# 5vacd.net
KiCad netlist of a schematic drawn in EAGLE
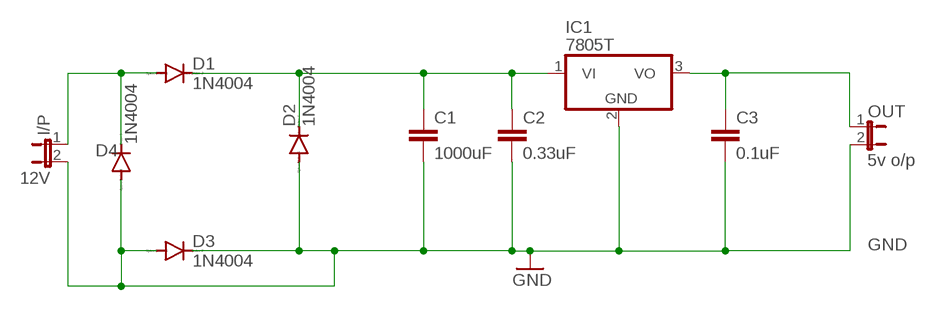
[diagram p0: schematic, sheet 1]

(export (version "E")
  (design (tool "Eeschema 10.0.6"))
  (components
    (comp (ref "C1")
      (value "1000uF")
      (footprint "eagle-import:C2.5-3")
      (fields (field (name "POPULARITY") "1000"))
      (libsource (lib "eagle-import") (part "C2,5-3"))
    )
    (comp (ref "C2")
      (value "0.33uF")
      (footprint "eagle-import:C2.5-3")
      (libsource (lib "eagle-import") (part "C2,5-3"))
    )
    (comp (ref "C3")
      (value "0.1uF")
      (footprint "eagle-import:C2.5-3")
      (libsource (lib "eagle-import") (part "C2,5-3"))
    )
    (comp (ref "D1")
      (value "1N4004")
      (footprint "eagle-import:DO41-10")
      (libsource (lib "eagle-import") (part "1N4004"))
    )
    (comp (ref "D2")
      (value "1N4004")
      (footprint "eagle-import:DO41-10")
      (libsource (lib "eagle-import") (part "1N4004"))
    )
    (comp (ref "D3")
      (value "1N4004")
      (footprint "eagle-import:DO41-10")
      (libsource (lib "eagle-import") (part "1N4004"))
    )
    (comp (ref "D4")
      (value "1N4004")
      (footprint "eagle-import:DO41-10")
      (libsource (lib "eagle-import") (part "1N4004"))
    )
    (comp (ref "I/P")
      (value "12V")
      (footprint "eagle-import:JP1")
      (libsource (lib "eagle-import") (part "JP1E"))
    )
    (comp (ref "IC1")
      (value "7805T")
      (footprint "eagle-import:TO220H")
      (libsource (lib "eagle-import") (part "78T05"))
    )
    (comp (ref "OUT")
      (value "5v o/p")
      (footprint "eagle-import:JP1")
      (libsource (lib "eagle-import") (part "JP1E"))
    )
  )
  (nets
    (net (code "1") (name "GND") (class "Default")
      (node (ref "C1") (pin "2") (pinfunction "2_2") (pintype "passive"))
      (node (ref "C2") (pin "2") (pinfunction "2_2") (pintype "passive"))
      (node (ref "C3") (pin "2") (pinfunction "2_2") (pintype "passive"))
      (node (ref "D2") (pin "A") (pinfunction "A_A") (pintype "passive"))
      (node (ref "D3") (pin "A") (pinfunction "A_A") (pintype "passive"))
      (node (ref "D3") (pin "C") (pinfunction "C_C") (pintype "passive"))
      (node (ref "D4") (pin "A") (pinfunction "A_A") (pintype "passive"))
      (node (ref "I/P") (pin "2") (pinfunction "2_2") (pintype "passive"))
      (node (ref "IC1") (pin "2") (pinfunction "GND_2") (pintype "passive"))
      (node (ref "OUT") (pin "2") (pinfunction "2_2") (pintype "passive"))
    )
    (net (code "2") (name "Net-(D1-PadA)") (class "Default")
      (node (ref "D1") (pin "A") (pinfunction "A_A") (pintype "passive"))
      (node (ref "D4") (pin "C") (pinfunction "C_C") (pintype "passive"))
      (node (ref "I/P") (pin "1") (pinfunction "1_1") (pintype "passive"))
    )
    (net (code "3") (name "Net-(IC1-VI)") (class "Default")
      (node (ref "C1") (pin "1") (pinfunction "1_1") (pintype "passive"))
      (node (ref "C2") (pin "1") (pinfunction "1_1") (pintype "passive"))
      (node (ref "D1") (pin "C") (pinfunction "C_C") (pintype "passive"))
      (node (ref "D2") (pin "C") (pinfunction "C_C") (pintype "passive"))
      (node (ref "IC1") (pin "1") (pinfunction "VI_1") (pintype "input"))
    )
    (net (code "4") (name "Net-(IC1-VO)") (class "Default")
      (node (ref "C3") (pin "1") (pinfunction "1_1") (pintype "passive"))
      (node (ref "IC1") (pin "3") (pinfunction "VO_3") (pintype "passive"))
      (node (ref "OUT") (pin "1") (pinfunction "1_1") (pintype "passive"))
    )
  )
)
